# MARS_GPIO_MISC.net
KiCad netlist of a schematic drawn in Altium Designer
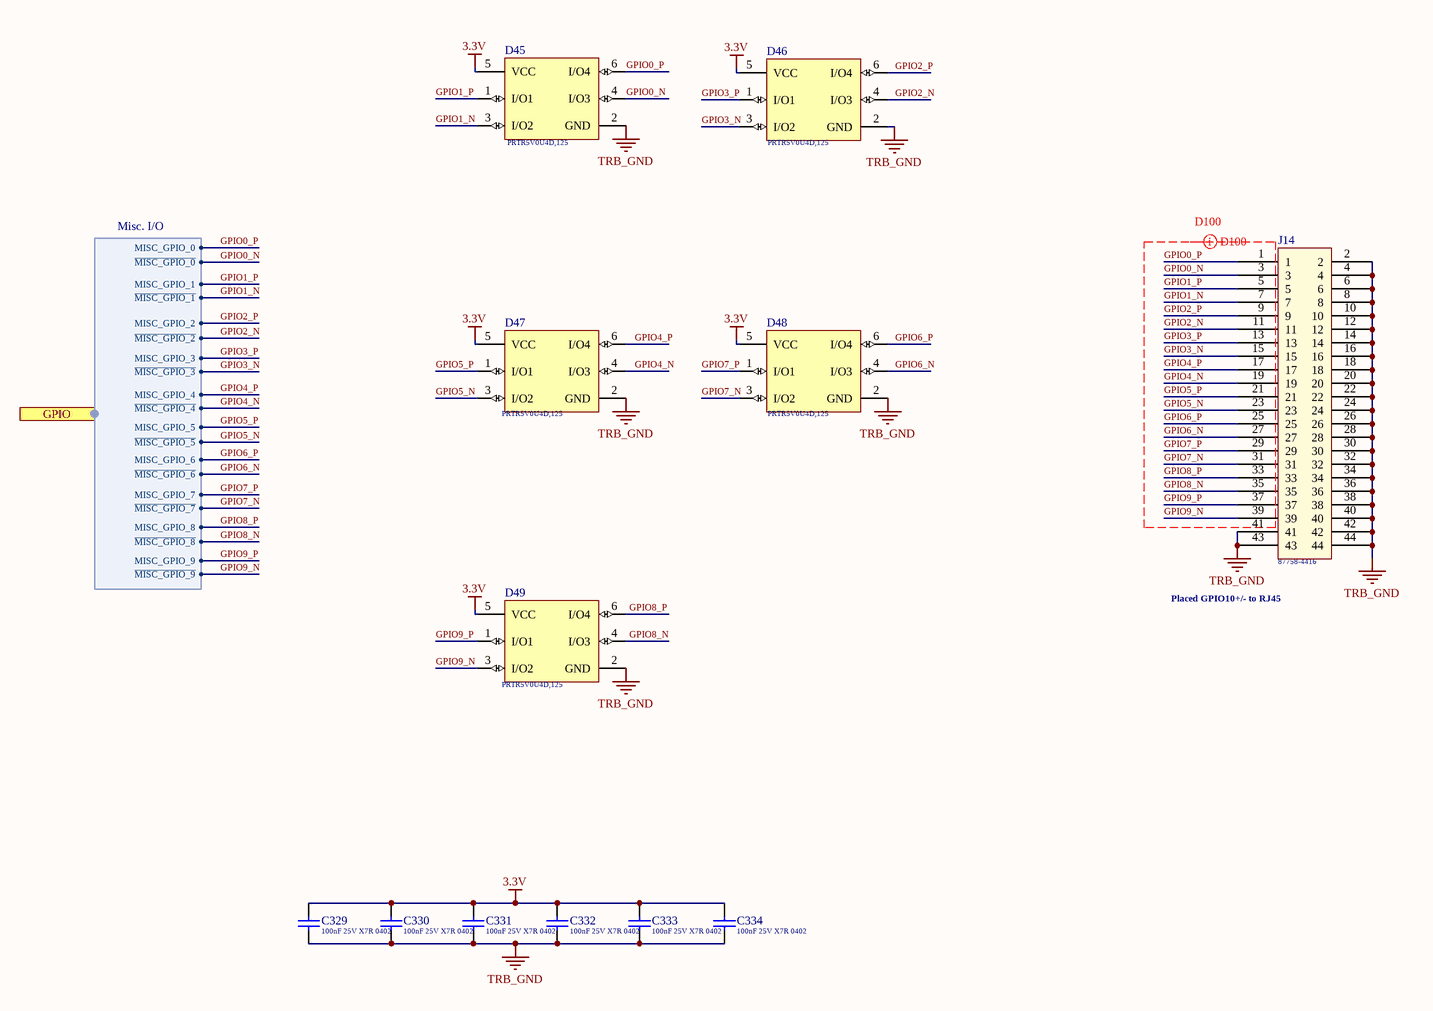
[diagram p0: MARS_GPIO_MISC.SchDoc]

(export (version "E")
  (design (tool "Eeschema 10.0.6"))
  (components
    (comp (ref "C329")
      (value "Cap_Taiyo_Yuden_TMK105B7104KV-FR_100nF")
      (footprint "Cap_Taiyo_Yuden_TMK105B7104KV-FR_100nF")
      (description "CAP CER 100nF 25V X7R 0402")
      (fields (field (name "CAPACITANCE") "100nF 25V X7R 0402"))
      (libsource (lib "Cap_Taiyo_Yuden_TMK105B7104KV-FR_100nF") (part "Cap_Taiyo_Yuden_TMK105B7104KV-FR_100nF"))
    )
    (comp (ref "C330")
      (value "Cap_Taiyo_Yuden_TMK105B7104KV-FR_100nF")
      (footprint "Cap_Taiyo_Yuden_TMK105B7104KV-FR_100nF")
      (description "CAP CER 100nF 25V X7R 0402")
      (fields (field (name "CAPACITANCE") "100nF 25V X7R 0402"))
      (libsource (lib "Cap_Taiyo_Yuden_TMK105B7104KV-FR_100nF") (part "Cap_Taiyo_Yuden_TMK105B7104KV-FR_100nF"))
    )
    (comp (ref "C331")
      (value "Cap_Taiyo_Yuden_TMK105B7104KV-FR_100nF")
      (footprint "Cap_Taiyo_Yuden_TMK105B7104KV-FR_100nF")
      (description "CAP CER 100nF 25V X7R 0402")
      (fields (field (name "CAPACITANCE") "100nF 25V X7R 0402"))
      (libsource (lib "Cap_Taiyo_Yuden_TMK105B7104KV-FR_100nF") (part "Cap_Taiyo_Yuden_TMK105B7104KV-FR_100nF"))
    )
    (comp (ref "C332")
      (value "Cap_Taiyo_Yuden_TMK105B7104KV-FR_100nF")
      (footprint "Cap_Taiyo_Yuden_TMK105B7104KV-FR_100nF")
      (description "CAP CER 100nF 25V X7R 0402")
      (fields (field (name "CAPACITANCE") "100nF 25V X7R 0402"))
      (libsource (lib "Cap_Taiyo_Yuden_TMK105B7104KV-FR_100nF") (part "Cap_Taiyo_Yuden_TMK105B7104KV-FR_100nF"))
    )
    (comp (ref "C333")
      (value "Cap_Taiyo_Yuden_TMK105B7104KV-FR_100nF")
      (footprint "Cap_Taiyo_Yuden_TMK105B7104KV-FR_100nF")
      (description "CAP CER 100nF 25V X7R 0402")
      (fields (field (name "CAPACITANCE") "100nF 25V X7R 0402"))
      (libsource (lib "Cap_Taiyo_Yuden_TMK105B7104KV-FR_100nF") (part "Cap_Taiyo_Yuden_TMK105B7104KV-FR_100nF"))
    )
    (comp (ref "C334")
      (value "Cap_Taiyo_Yuden_TMK105B7104KV-FR_100nF")
      (footprint "Cap_Taiyo_Yuden_TMK105B7104KV-FR_100nF")
      (description "CAP CER 100nF 25V X7R 0402")
      (fields (field (name "CAPACITANCE") "100nF 25V X7R 0402"))
      (libsource (lib "Cap_Taiyo_Yuden_TMK105B7104KV-FR_100nF") (part "Cap_Taiyo_Yuden_TMK105B7104KV-FR_100nF"))
    )
    (comp (ref "D45")
      (value "PRTR5V0U4D,125")
      (footprint "PRTR5V0U4D,125")
      (description "ESD Suppressors / TVS Diodes 5.5V QUAD R-R ESD ULTRA LOW CAP")
      (libsource (lib "PRTR5V0U4D,125") (part "PRTR5V0U4D,125"))
    )
    (comp (ref "D46")
      (value "PRTR5V0U4D,125")
      (footprint "PRTR5V0U4D,125")
      (description "ESD Suppressors / TVS Diodes 5.5V QUAD R-R ESD ULTRA LOW CAP")
      (libsource (lib "PRTR5V0U4D,125") (part "PRTR5V0U4D,125"))
    )
    (comp (ref "D47")
      (value "PRTR5V0U4D,125")
      (footprint "PRTR5V0U4D,125")
      (description "ESD Suppressors / TVS Diodes 5.5V QUAD R-R ESD ULTRA LOW CAP")
      (libsource (lib "PRTR5V0U4D,125") (part "PRTR5V0U4D,125"))
    )
    (comp (ref "D48")
      (value "PRTR5V0U4D,125")
      (footprint "PRTR5V0U4D,125")
      (description "ESD Suppressors / TVS Diodes 5.5V QUAD R-R ESD ULTRA LOW CAP")
      (libsource (lib "PRTR5V0U4D,125") (part "PRTR5V0U4D,125"))
    )
    (comp (ref "D49")
      (value "PRTR5V0U4D,125")
      (footprint "PRTR5V0U4D,125")
      (description "ESD Suppressors / TVS Diodes 5.5V QUAD R-R ESD ULTRA LOW CAP")
      (libsource (lib "PRTR5V0U4D,125") (part "PRTR5V0U4D,125"))
    )
    (comp (ref "J14")
      (value "Header_Molex_87758-4416_44POS")
      (footprint "Header_Molex_87758-4416_44POS")
      (description "Headers & Wire Housings VERT HEADER 44P Lead Free")
      (fields (field (name "SERIES") "87758-4416"))
      (libsource (lib "Header_Molex_87758-4416_44POS") (part "Header_Molex_87758-4416_44POS"))
    )
  )
  (nets
    (net (code "3") (name "/GPIO0_N") (class "Default")
      (node (ref "D45") (pin "4") (pinfunction "I/O3_4") (pintype "bidirectional"))
      (node (ref "J14") (pin "3") (pinfunction "3_3") (pintype "passive"))
    )
    (net (code "4") (name "/GPIO0_P") (class "Default")
      (node (ref "D45") (pin "6") (pinfunction "I/O4_6") (pintype "bidirectional"))
      (node (ref "J14") (pin "1") (pinfunction "1_1") (pintype "passive"))
    )
    (net (code "5") (name "/GPIO1_N") (class "Default")
      (node (ref "D45") (pin "3") (pinfunction "I/O2_3") (pintype "bidirectional"))
      (node (ref "J14") (pin "7") (pinfunction "7_7") (pintype "passive"))
    )
    (net (code "6") (name "/GPIO1_P") (class "Default")
      (node (ref "D45") (pin "1") (pinfunction "I/O1_1") (pintype "bidirectional"))
      (node (ref "J14") (pin "5") (pinfunction "5_5") (pintype "passive"))
    )
    (net (code "7") (name "/GPIO2_N") (class "Default")
      (node (ref "D46") (pin "4") (pinfunction "I/O3_4") (pintype "bidirectional"))
      (node (ref "J14") (pin "11") (pinfunction "11_11") (pintype "passive"))
    )
    (net (code "8") (name "/GPIO2_P") (class "Default")
      (node (ref "D46") (pin "6") (pinfunction "I/O4_6") (pintype "bidirectional"))
      (node (ref "J14") (pin "9") (pinfunction "9_9") (pintype "passive"))
    )
    (net (code "9") (name "/GPIO3_N") (class "Default")
      (node (ref "D46") (pin "3") (pinfunction "I/O2_3") (pintype "bidirectional"))
      (node (ref "J14") (pin "15") (pinfunction "15_15") (pintype "passive"))
    )
    (net (code "10") (name "/GPIO3_P") (class "Default")
      (node (ref "D46") (pin "1") (pinfunction "I/O1_1") (pintype "bidirectional"))
      (node (ref "J14") (pin "13") (pinfunction "13_13") (pintype "passive"))
    )
    (net (code "11") (name "/GPIO4_N") (class "Default")
      (node (ref "D47") (pin "4") (pinfunction "I/O3_4") (pintype "bidirectional"))
      (node (ref "J14") (pin "19") (pinfunction "19_19") (pintype "passive"))
    )
    (net (code "12") (name "/GPIO4_P") (class "Default")
      (node (ref "D47") (pin "6") (pinfunction "I/O4_6") (pintype "bidirectional"))
      (node (ref "J14") (pin "17") (pinfunction "17_17") (pintype "passive"))
    )
    (net (code "13") (name "/GPIO5_N") (class "Default")
      (node (ref "D47") (pin "3") (pinfunction "I/O2_3") (pintype "bidirectional"))
      (node (ref "J14") (pin "23") (pinfunction "23_23") (pintype "passive"))
    )
    (net (code "14") (name "/GPIO5_P") (class "Default")
      (node (ref "D47") (pin "1") (pinfunction "I/O1_1") (pintype "bidirectional"))
      (node (ref "J14") (pin "21") (pinfunction "21_21") (pintype "passive"))
    )
    (net (code "15") (name "/GPIO6_N") (class "Default")
      (node (ref "D48") (pin "4") (pinfunction "I/O3_4") (pintype "bidirectional"))
      (node (ref "J14") (pin "27") (pinfunction "27_27") (pintype "passive"))
    )
    (net (code "16") (name "/GPIO6_P") (class "Default")
      (node (ref "D48") (pin "6") (pinfunction "I/O4_6") (pintype "bidirectional"))
      (node (ref "J14") (pin "25") (pinfunction "25_25") (pintype "passive"))
    )
    (net (code "17") (name "/GPIO7_N") (class "Default")
      (node (ref "D48") (pin "3") (pinfunction "I/O2_3") (pintype "bidirectional"))
      (node (ref "J14") (pin "31") (pinfunction "31_31") (pintype "passive"))
    )
    (net (code "18") (name "/GPIO7_P") (class "Default")
      (node (ref "D48") (pin "1") (pinfunction "I/O1_1") (pintype "bidirectional"))
      (node (ref "J14") (pin "29") (pinfunction "29_29") (pintype "passive"))
    )
    (net (code "19") (name "/GPIO8_N") (class "Default")
      (node (ref "D49") (pin "4") (pinfunction "I/O3_4") (pintype "bidirectional"))
      (node (ref "J14") (pin "35") (pinfunction "35_35") (pintype "passive"))
    )
    (net (code "20") (name "/GPIO8_P") (class "Default")
      (node (ref "D49") (pin "6") (pinfunction "I/O4_6") (pintype "bidirectional"))
      (node (ref "J14") (pin "33") (pinfunction "33_33") (pintype "passive"))
    )
    (net (code "21") (name "/GPIO9_N") (class "Default")
      (node (ref "D49") (pin "3") (pinfunction "I/O2_3") (pintype "bidirectional"))
      (node (ref "J14") (pin "39") (pinfunction "39_39") (pintype "passive"))
    )
    (net (code "22") (name "/GPIO9_P") (class "Default")
      (node (ref "D49") (pin "1") (pinfunction "I/O1_1") (pintype "bidirectional"))
      (node (ref "J14") (pin "37") (pinfunction "37_37") (pintype "passive"))
    )
    (net (code "24") (name "3.3V") (class "Default")
      (node (ref "C329") (pin "2") (pinfunction "2_2") (pintype "passive"))
      (node (ref "C330") (pin "2") (pinfunction "2_2") (pintype "passive"))
      (node (ref "C331") (pin "2") (pinfunction "2_2") (pintype "passive"))
      (node (ref "C332") (pin "2") (pinfunction "2_2") (pintype "passive"))
      (node (ref "C333") (pin "2") (pinfunction "2_2") (pintype "passive"))
      (node (ref "C334") (pin "2") (pinfunction "2_2") (pintype "passive"))
      (node (ref "D45") (pin "5") (pinfunction "VCC_5") (pintype "power_in"))
      (node (ref "D46") (pin "5") (pinfunction "VCC_5") (pintype "power_in"))
      (node (ref "D47") (pin "5") (pinfunction "VCC_5") (pintype "power_in"))
      (node (ref "D48") (pin "5") (pinfunction "VCC_5") (pintype "power_in"))
      (node (ref "D49") (pin "5") (pinfunction "VCC_5") (pintype "power_in"))
    )
    (net (code "25") (name "TRB_GND") (class "Default")
      (node (ref "C329") (pin "1") (pinfunction "1_1") (pintype "passive"))
      (node (ref "C330") (pin "1") (pinfunction "1_1") (pintype "passive"))
      (node (ref "C331") (pin "1") (pinfunction "1_1") (pintype "passive"))
      (node (ref "C332") (pin "1") (pinfunction "1_1") (pintype "passive"))
      (node (ref "C333") (pin "1") (pinfunction "1_1") (pintype "passive"))
      (node (ref "C334") (pin "1") (pinfunction "1_1") (pintype "passive"))
      (node (ref "D45") (pin "2") (pinfunction "GND_2") (pintype "power_in"))
      (node (ref "D46") (pin "2") (pinfunction "GND_2") (pintype "power_in"))
      (node (ref "D47") (pin "2") (pinfunction "GND_2") (pintype "power_in"))
      (node (ref "D48") (pin "2") (pinfunction "GND_2") (pintype "power_in"))
      (node (ref "D49") (pin "2") (pinfunction "GND_2") (pintype "power_in"))
      (node (ref "J14") (pin "10") (pinfunction "10_10") (pintype "passive"))
      (node (ref "J14") (pin "12") (pinfunction "12_12") (pintype "passive"))
      (node (ref "J14") (pin "14") (pinfunction "14_14") (pintype "passive"))
      (node (ref "J14") (pin "16") (pinfunction "16_16") (pintype "passive"))
      (node (ref "J14") (pin "18") (pinfunction "18_18") (pintype "passive"))
      (node (ref "J14") (pin "2") (pinfunction "2_2") (pintype "passive"))
      (node (ref "J14") (pin "20") (pinfunction "20_20") (pintype "passive"))
      (node (ref "J14") (pin "22") (pinfunction "22_22") (pintype "passive"))
      (node (ref "J14") (pin "24") (pinfunction "24_24") (pintype "passive"))
      (node (ref "J14") (pin "26") (pinfunction "26_26") (pintype "passive"))
      (node (ref "J14") (pin "28") (pinfunction "28_28") (pintype "passive"))
      (node (ref "J14") (pin "30") (pinfunction "30_30") (pintype "passive"))
      (node (ref "J14") (pin "32") (pinfunction "32_32") (pintype "passive"))
      (node (ref "J14") (pin "34") (pinfunction "34_34") (pintype "passive"))
      (node (ref "J14") (pin "36") (pinfunction "36_36") (pintype "passive"))
      (node (ref "J14") (pin "38") (pinfunction "38_38") (pintype "passive"))
      (node (ref "J14") (pin "4") (pinfunction "4_4") (pintype "passive"))
      (node (ref "J14") (pin "40") (pinfunction "40_40") (pintype "passive"))
      (node (ref "J14") (pin "41") (pinfunction "41_41") (pintype "passive"))
      (node (ref "J14") (pin "42") (pinfunction "42_42") (pintype "passive"))
      (node (ref "J14") (pin "43") (pinfunction "43_43") (pintype "passive"))
      (node (ref "J14") (pin "44") (pinfunction "44_44") (pintype "passive"))
      (node (ref "J14") (pin "6") (pinfunction "6_6") (pintype "passive"))
      (node (ref "J14") (pin "8") (pinfunction "8_8") (pintype "passive"))
    )
  )
)
